# 4_-DISPLAY_ERC12864FS.net
KiCad netlist of a schematic drawn in Altium Designer
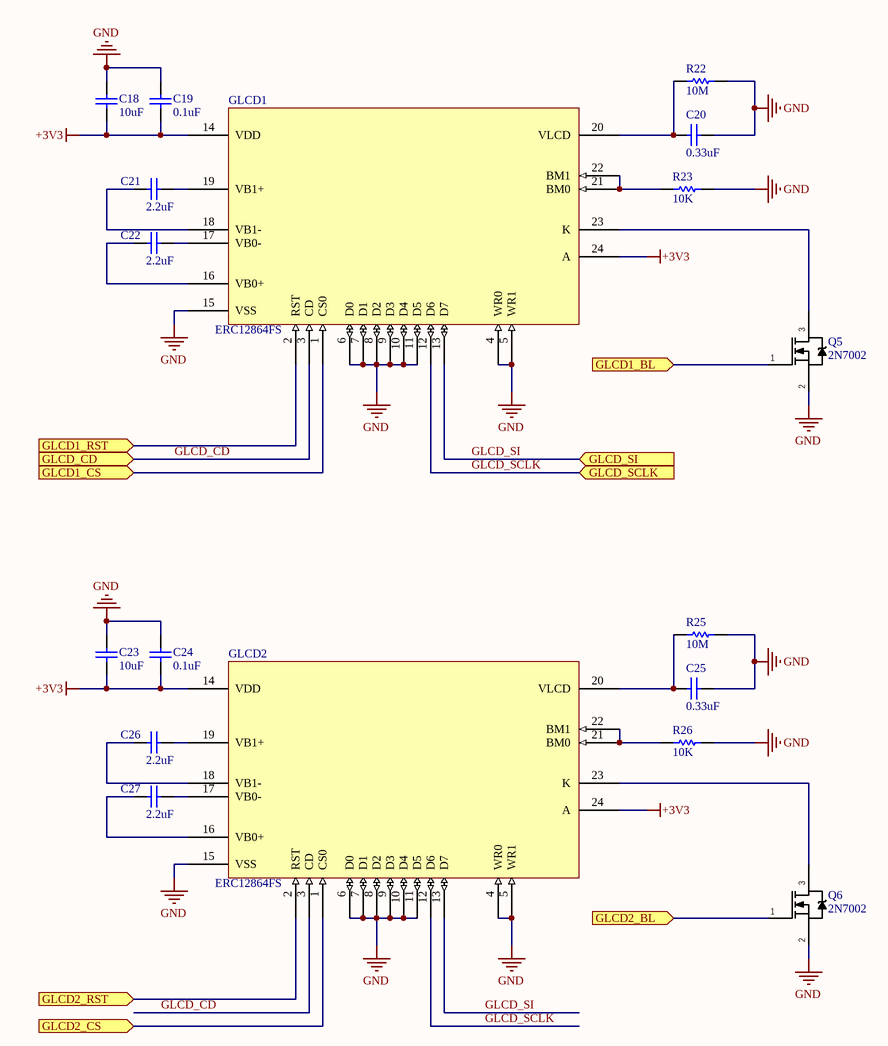
[diagram p0: [4]-DISPLAY_ERC12864FS.SchDoc]

(export (version "E")
  (design (tool "Eeschema 10.0.6"))
  (components
    (comp (ref "C18")
      (value "10uF")
      (footprint "CAPC1608N")
      (description "CAP CER 10UF 10V X5R 0603")
      (fields (field (name "TOLERANCE") "10%") (field (name "VOLTAGE") "10V"))
      (libsource (lib "bitsnio") (part "GRM188R61A106KE69D"))
    )
    (comp (ref "C19")
      (value "0.1uF")
      (footprint "CAPC1608N")
      (description "CAP CER 0.1UF 25V X7R 0603")
      (fields (field (name "TOLERANCE") "10%") (field (name "VOLTAGE") "25V"))
      (libsource (lib "bitsnio") (part "CC0603KRX7R8BB104"))
    )
    (comp (ref "C20")
      (value "0.33uF")
      (footprint "CAPC2012N")
      (description "CAP CER 0.33UF 50V X7R 0805")
      (fields (field (name "TOLERANCE") "10 %"))
      (libsource (lib "bitsnio") (part "C0805C334K5RACAUTO"))
    )
    (comp (ref "C21")
      (value "2.2uF")
      (footprint "CAPC2012N")
      (description "CAP CER 2.2UF 16V X7R 0805")
      (fields (field (name "TOLERANCE") "10%") (field (name "VOLTAGE") "16V"))
      (libsource (lib "bitsnio") (part "C2012X7R1C225K125AB"))
    )
    (comp (ref "C22")
      (value "2.2uF")
      (footprint "CAPC2012N")
      (description "CAP CER 2.2UF 16V X7R 0805")
      (fields (field (name "TOLERANCE") "10%") (field (name "VOLTAGE") "16V"))
      (libsource (lib "bitsnio") (part "C2012X7R1C225K125AB"))
    )
    (comp (ref "C23")
      (value "10uF")
      (footprint "CAPC1608N")
      (description "CAP CER 10UF 10V X5R 0603")
      (fields (field (name "TOLERANCE") "10%") (field (name "VOLTAGE") "10V"))
      (libsource (lib "bitsnio") (part "GRM188R61A106KE69D"))
    )
    (comp (ref "C24")
      (value "0.1uF")
      (footprint "CAPC1608N")
      (description "CAP CER 0.1UF 25V X7R 0603")
      (fields (field (name "TOLERANCE") "10%") (field (name "VOLTAGE") "25V"))
      (libsource (lib "bitsnio") (part "CC0603KRX7R8BB104"))
    )
    (comp (ref "C25")
      (value "0.33uF")
      (footprint "CAPC2012N")
      (description "CAP CER 0.33UF 50V X7R 0805")
      (fields (field (name "TOLERANCE") "10 %"))
      (libsource (lib "bitsnio") (part "C0805C334K5RACAUTO"))
    )
    (comp (ref "C26")
      (value "2.2uF")
      (footprint "CAPC2012N")
      (description "CAP CER 2.2UF 16V X7R 0805")
      (fields (field (name "TOLERANCE") "10%") (field (name "VOLTAGE") "16V"))
      (libsource (lib "bitsnio") (part "C2012X7R1C225K125AB"))
    )
    (comp (ref "C27")
      (value "2.2uF")
      (footprint "CAPC2012N")
      (description "CAP CER 2.2UF 16V X7R 0805")
      (fields (field (name "TOLERANCE") "10%") (field (name "VOLTAGE") "16V"))
      (libsource (lib "bitsnio") (part "C2012X7R1C225K125AB"))
    )
    (comp (ref "GLCD1")
      (value "ERC12864FS")
      (footprint "ERC12864FS")
      (description "SERIAL SPI 2.8\"GLCD 128x64 UC1701 CONTROLLER")
      (libsource (lib "bitsnio") (part "ERC12864FS-655"))
    )
    (comp (ref "GLCD2")
      (value "ERC12864FS")
      (footprint "ERC12864FS")
      (description "SERIAL SPI 2.8\"GLCD 128x64 UC1701 CONTROLLER")
      (libsource (lib "bitsnio") (part "ERC12864FS-655"))
    )
    (comp (ref "Q5")
      (value "2N7002")
      (footprint "SOT23-3N")
      (description "MOSFET N-CH 60V 115MA SOT-23")
      (fields (field (name "VOLTAGE") "60V"))
      (libsource (lib "bitsnio") (part "2N7002"))
    )
    (comp (ref "Q6")
      (value "2N7002")
      (footprint "SOT23-3N")
      (description "MOSFET N-CH 60V 115MA SOT-23")
      (fields (field (name "VOLTAGE") "60V"))
      (libsource (lib "bitsnio") (part "2N7002"))
    )
    (comp (ref "R22")
      (value "10M")
      (footprint "RESC1608N")
      (description "RES SMD 10M OHM 5% 1/10W 0603")
      (fields (field (name "TOLERANCE") "5%"))
      (libsource (lib "bitsnio") (part "CR0603-JW-106ELF"))
    )
    (comp (ref "R23")
      (value "10K")
      (footprint "RESC1608N")
      (description "RES SMD 10K OHM 5% 1/10W 0603")
      (fields (field (name "TOLERANCE") "5%"))
      (libsource (lib "bitsnio") (part "AC0603JR-0710KL"))
    )
    (comp (ref "R25")
      (value "10M")
      (footprint "RESC1608N")
      (description "RES SMD 10M OHM 5% 1/10W 0603")
      (fields (field (name "TOLERANCE") "5%"))
      (libsource (lib "bitsnio") (part "CR0603-JW-106ELF"))
    )
    (comp (ref "R26")
      (value "10K")
      (footprint "RESC1608N")
      (description "RES SMD 10K OHM 5% 1/10W 0603")
      (fields (field (name "TOLERANCE") "5%"))
      (libsource (lib "bitsnio") (part "AC0603JR-0710KL"))
    )
  )
  (nets
    (net (code "1") (name "+3V3") (class "Default")
      (node (ref "C18") (pin "1") (pinfunction "1_1") (pintype "passive"))
      (node (ref "C19") (pin "1") (pinfunction "1_1") (pintype "passive"))
      (node (ref "C23") (pin "1") (pinfunction "1_1") (pintype "passive"))
      (node (ref "C24") (pin "1") (pinfunction "1_1") (pintype "passive"))
      (node (ref "GLCD1") (pin "14") (pinfunction "VDD_14") (pintype "power_in"))
      (node (ref "GLCD1") (pin "24") (pinfunction "A_24") (pintype "passive"))
      (node (ref "GLCD2") (pin "14") (pinfunction "VDD_14") (pintype "power_in"))
      (node (ref "GLCD2") (pin "24") (pinfunction "A_24") (pintype "passive"))
    )
    (net (code "2") (name "/GLCD1_BL") (class "Default")
      (node (ref "Q5") (pin "1") (pinfunction "G_1") (pintype "passive"))
    )
    (net (code "3") (name "/GLCD1_CS") (class "Default")
      (node (ref "GLCD1") (pin "1") (pinfunction "CS0_1") (pintype "input"))
    )
    (net (code "4") (name "/GLCD1_RST") (class "Default")
      (node (ref "GLCD1") (pin "2") (pinfunction "RST_2") (pintype "input"))
    )
    (net (code "5") (name "/GLCD2_BL") (class "Default")
      (node (ref "Q6") (pin "1") (pinfunction "G_1") (pintype "passive"))
    )
    (net (code "6") (name "/GLCD2_CS") (class "Default")
      (node (ref "GLCD2") (pin "1") (pinfunction "CS0_1") (pintype "input"))
    )
    (net (code "7") (name "/GLCD2_RST") (class "Default")
      (node (ref "GLCD2") (pin "2") (pinfunction "RST_2") (pintype "input"))
    )
    (net (code "8") (name "/GLCD_CD") (class "Default")
      (node (ref "GLCD1") (pin "3") (pinfunction "CD_3") (pintype "input"))
      (node (ref "GLCD2") (pin "3") (pinfunction "CD_3") (pintype "input"))
    )
    (net (code "9") (name "/GLCD_SCLK") (class "Default")
      (node (ref "GLCD1") (pin "12") (pinfunction "D6_12") (pintype "bidirectional"))
      (node (ref "GLCD2") (pin "12") (pinfunction "D6_12") (pintype "bidirectional"))
    )
    (net (code "10") (name "/GLCD_SI") (class "Default")
      (node (ref "GLCD1") (pin "13") (pinfunction "D7_13") (pintype "bidirectional"))
      (node (ref "GLCD2") (pin "13") (pinfunction "D7_13") (pintype "bidirectional"))
    )
    (net (code "11") (name "GND") (class "Default")
      (node (ref "C18") (pin "2") (pinfunction "2_2") (pintype "passive"))
      (node (ref "C19") (pin "2") (pinfunction "2_2") (pintype "passive"))
      (node (ref "C20") (pin "2") (pinfunction "2_2") (pintype "passive"))
      (node (ref "C23") (pin "2") (pinfunction "2_2") (pintype "passive"))
      (node (ref "C24") (pin "2") (pinfunction "2_2") (pintype "passive"))
      (node (ref "C25") (pin "2") (pinfunction "2_2") (pintype "passive"))
      (node (ref "GLCD1") (pin "10") (pinfunction "D4_10") (pintype "bidirectional"))
      (node (ref "GLCD1") (pin "11") (pinfunction "D5_11") (pintype "bidirectional"))
      (node (ref "GLCD1") (pin "15") (pinfunction "VSS_15") (pintype "power_in"))
      (node (ref "GLCD1") (pin "4") (pinfunction "WR0_4") (pintype "input"))
      (node (ref "GLCD1") (pin "5") (pinfunction "WR1_5") (pintype "input"))
      (node (ref "GLCD1") (pin "6") (pinfunction "D0_6") (pintype "bidirectional"))
      (node (ref "GLCD1") (pin "7") (pinfunction "D1_7") (pintype "bidirectional"))
      (node (ref "GLCD1") (pin "8") (pinfunction "D2_8") (pintype "bidirectional"))
      (node (ref "GLCD1") (pin "9") (pinfunction "D3_9") (pintype "bidirectional"))
      (node (ref "GLCD2") (pin "10") (pinfunction "D4_10") (pintype "bidirectional"))
      (node (ref "GLCD2") (pin "11") (pinfunction "D5_11") (pintype "bidirectional"))
      (node (ref "GLCD2") (pin "15") (pinfunction "VSS_15") (pintype "power_in"))
      (node (ref "GLCD2") (pin "4") (pinfunction "WR0_4") (pintype "input"))
      (node (ref "GLCD2") (pin "5") (pinfunction "WR1_5") (pintype "input"))
      (node (ref "GLCD2") (pin "6") (pinfunction "D0_6") (pintype "bidirectional"))
      (node (ref "GLCD2") (pin "7") (pinfunction "D1_7") (pintype "bidirectional"))
      (node (ref "GLCD2") (pin "8") (pinfunction "D2_8") (pintype "bidirectional"))
      (node (ref "GLCD2") (pin "9") (pinfunction "D3_9") (pintype "bidirectional"))
      (node (ref "Q5") (pin "2") (pinfunction "S_2") (pintype "passive"))
      (node (ref "Q6") (pin "2") (pinfunction "S_2") (pintype "passive"))
      (node (ref "R22") (pin "2") (pinfunction "2_2") (pintype "passive"))
      (node (ref "R23") (pin "1") (pinfunction "1_1") (pintype "passive"))
      (node (ref "R25") (pin "2") (pinfunction "2_2") (pintype "passive"))
      (node (ref "R26") (pin "1") (pinfunction "1_1") (pintype "passive"))
    )
    (net (code "12") (name "Net-(GLCD1-BM0)") (class "Default")
      (node (ref "GLCD1") (pin "21") (pinfunction "BM0_21") (pintype "input"))
      (node (ref "GLCD1") (pin "22") (pinfunction "BM1_22") (pintype "input"))
      (node (ref "R23") (pin "2") (pinfunction "2_2") (pintype "passive"))
    )
    (net (code "13") (name "Net-(GLCD1-K)") (class "Default")
      (node (ref "GLCD1") (pin "23") (pinfunction "K_23") (pintype "passive"))
      (node (ref "Q5") (pin "3") (pinfunction "D_3") (pintype "passive"))
    )
    (net (code "14") (name "Net-(GLCD1-VB0+)") (class "Default")
      (node (ref "C22") (pin "1") (pinfunction "1_1") (pintype "passive"))
      (node (ref "GLCD1") (pin "16") (pinfunction "VB0+_16") (pintype "passive"))
    )
    (net (code "15") (name "Net-(GLCD1-VB0-)") (class "Default")
      (node (ref "C22") (pin "2") (pinfunction "2_2") (pintype "passive"))
      (node (ref "GLCD1") (pin "17") (pinfunction "VB0-_17") (pintype "passive"))
    )
    (net (code "16") (name "Net-(GLCD1-VB1+)") (class "Default")
      (node (ref "C21") (pin "2") (pinfunction "2_2") (pintype "passive"))
      (node (ref "GLCD1") (pin "19") (pinfunction "VB1+_19") (pintype "passive"))
    )
    (net (code "17") (name "Net-(GLCD1-VB1-)") (class "Default")
      (node (ref "C21") (pin "1") (pinfunction "1_1") (pintype "passive"))
      (node (ref "GLCD1") (pin "18") (pinfunction "VB1-_18") (pintype "passive"))
    )
    (net (code "18") (name "Net-(GLCD1-VLCD)") (class "Default")
      (node (ref "C20") (pin "1") (pinfunction "1_1") (pintype "passive"))
      (node (ref "GLCD1") (pin "20") (pinfunction "VLCD_20") (pintype "power_in"))
      (node (ref "R22") (pin "1") (pinfunction "1_1") (pintype "passive"))
    )
    (net (code "19") (name "Net-(GLCD2-BM0)") (class "Default")
      (node (ref "GLCD2") (pin "21") (pinfunction "BM0_21") (pintype "input"))
      (node (ref "GLCD2") (pin "22") (pinfunction "BM1_22") (pintype "input"))
      (node (ref "R26") (pin "2") (pinfunction "2_2") (pintype "passive"))
    )
    (net (code "20") (name "Net-(GLCD2-K)") (class "Default")
      (node (ref "GLCD2") (pin "23") (pinfunction "K_23") (pintype "passive"))
      (node (ref "Q6") (pin "3") (pinfunction "D_3") (pintype "passive"))
    )
    (net (code "21") (name "Net-(GLCD2-VB0+)") (class "Default")
      (node (ref "C27") (pin "1") (pinfunction "1_1") (pintype "passive"))
      (node (ref "GLCD2") (pin "16") (pinfunction "VB0+_16") (pintype "passive"))
    )
    (net (code "22") (name "Net-(GLCD2-VB0-)") (class "Default")
      (node (ref "C27") (pin "2") (pinfunction "2_2") (pintype "passive"))
      (node (ref "GLCD2") (pin "17") (pinfunction "VB0-_17") (pintype "passive"))
    )
    (net (code "23") (name "Net-(GLCD2-VB1+)") (class "Default")
      (node (ref "C26") (pin "2") (pinfunction "2_2") (pintype "passive"))
      (node (ref "GLCD2") (pin "19") (pinfunction "VB1+_19") (pintype "passive"))
    )
    (net (code "24") (name "Net-(GLCD2-VB1-)") (class "Default")
      (node (ref "C26") (pin "1") (pinfunction "1_1") (pintype "passive"))
      (node (ref "GLCD2") (pin "18") (pinfunction "VB1-_18") (pintype "passive"))
    )
    (net (code "25") (name "Net-(GLCD2-VLCD)") (class "Default")
      (node (ref "C25") (pin "1") (pinfunction "1_1") (pintype "passive"))
      (node (ref "GLCD2") (pin "20") (pinfunction "VLCD_20") (pintype "power_in"))
      (node (ref "R25") (pin "1") (pinfunction "1_1") (pintype "passive"))
    )
  )
)
